# mems.net
KiCad netlist of a schematic drawn in Altium Designer
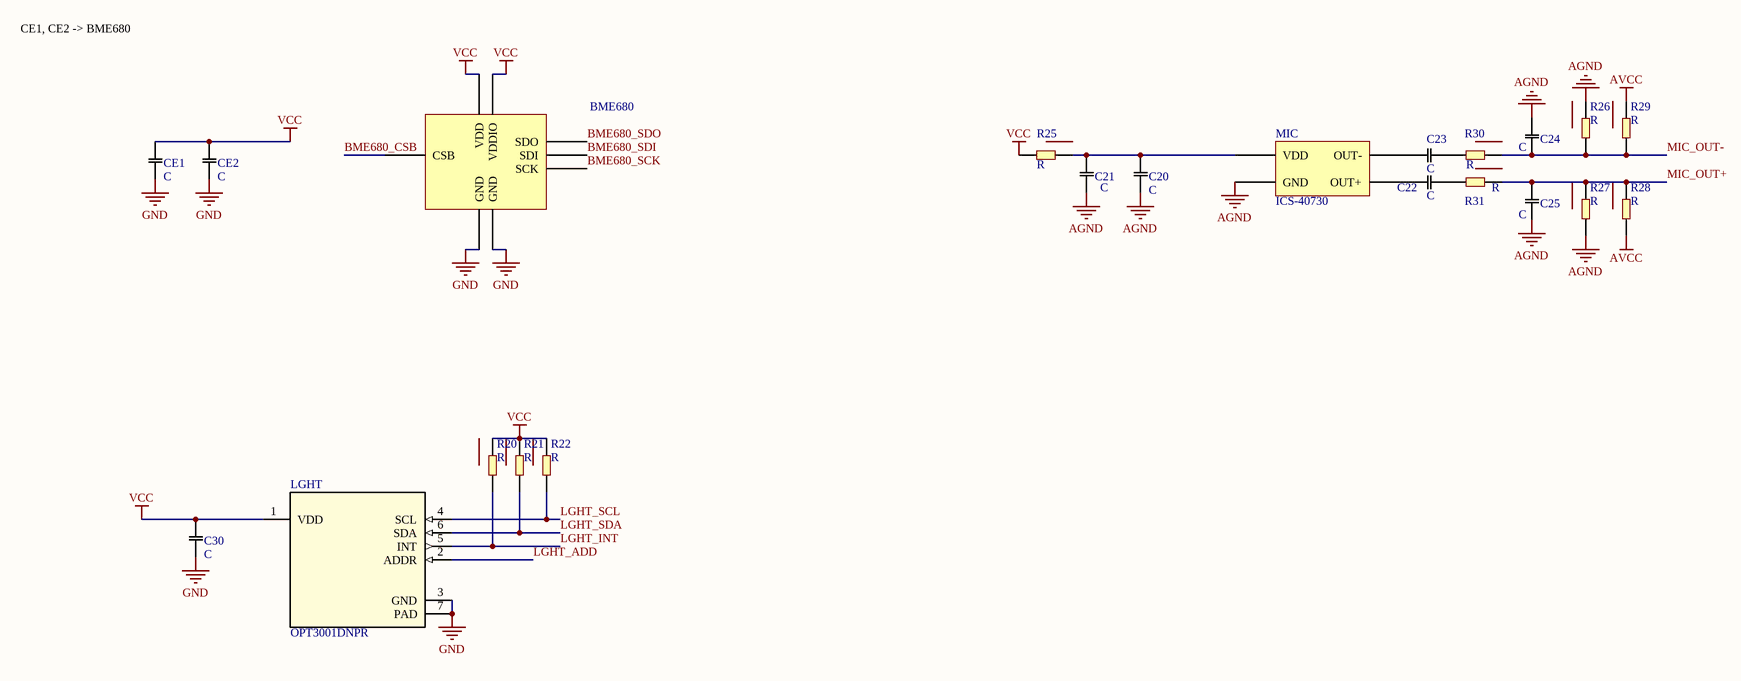
[diagram p0: mems.SchDoc]

(export (version "E")
  (design (tool "Eeschema 10.0.6"))
  (components
    (comp (ref "BME680") (value "~") (footprint "BME680") (libsource (lib "env_sens") (part "BME680")))
    (comp (ref "C20")
      (value "C")
      (footprint "402")
      (description "Capacitor")
      (libsource (lib "pass_comp") (part "C"))
    )
    (comp (ref "C21")
      (value "C")
      (footprint "402")
      (description "Capacitor")
      (libsource (lib "pass_comp") (part "C"))
    )
    (comp (ref "C22")
      (value "C")
      (footprint "402")
      (description "Capacitor")
      (libsource (lib "pass_comp") (part "C"))
    )
    (comp (ref "C23")
      (value "C")
      (footprint "402")
      (description "Capacitor")
      (libsource (lib "pass_comp") (part "C"))
    )
    (comp (ref "C24")
      (value "C")
      (footprint "402")
      (description "Capacitor")
      (libsource (lib "pass_comp") (part "C"))
    )
    (comp (ref "C25")
      (value "C")
      (footprint "402")
      (description "Capacitor")
      (libsource (lib "pass_comp") (part "C"))
    )
    (comp (ref "C30")
      (value "C")
      (footprint "402")
      (description "Capacitor")
      (libsource (lib "pass_comp") (part "C"))
    )
    (comp (ref "CE1")
      (value "C")
      (footprint "402")
      (description "Capacitor")
      (libsource (lib "pass_comp") (part "C"))
    )
    (comp (ref "CE2")
      (value "C")
      (footprint "402")
      (description "Capacitor")
      (libsource (lib "pass_comp") (part "C"))
    )
    (comp (ref "LGHT")
      (value "OPT3001DNPR")
      (footprint "DNP0006A")
      (description "Imported")
      (fields (field (name "PARTNUMBER") "OPT3001DNP") (field (name "MANUFACTURER") "Texas Instruments"))
      (libsource (lib "env_sens") (part "OPT3001DNPR"))
    )
    (comp (ref "MIC")
      (value "ICS-40730")
      (footprint "ICS-40730")
      (libsource (lib "env_sens") (part "ICS-40730"))
    )
    (comp (ref "R20")
      (value "R")
      (footprint "402")
      (description "Resistor")
      (libsource (lib "") (part "R_1"))
    )
    (comp (ref "R21")
      (value "R")
      (footprint "402")
      (description "Resistor")
      (libsource (lib "") (part "R_1"))
    )
    (comp (ref "R22")
      (value "R")
      (footprint "402")
      (description "Resistor")
      (libsource (lib "") (part "R_1"))
    )
    (comp (ref "R25")
      (value "R")
      (footprint "603")
      (description "Resistor")
      (libsource (lib "pass_comp") (part "R"))
    )
    (comp (ref "R26")
      (value "R")
      (footprint "402")
      (description "Resistor")
      (libsource (lib "") (part "R_1"))
    )
    (comp (ref "R27")
      (value "R")
      (footprint "402")
      (description "Resistor")
      (libsource (lib "") (part "R_1"))
    )
    (comp (ref "R28")
      (value "R")
      (footprint "402")
      (description "Resistor")
      (libsource (lib "") (part "R_1"))
    )
    (comp (ref "R29")
      (value "R")
      (footprint "402")
      (description "Resistor")
      (libsource (lib "") (part "R_1"))
    )
    (comp (ref "R30")
      (value "R")
      (footprint "402")
      (description "Resistor")
      (libsource (lib "pass_comp") (part "R"))
    )
    (comp (ref "R31")
      (value "R")
      (footprint "402")
      (description "Resistor")
      (libsource (lib "pass_comp") (part "R"))
    )
  )
  (nets
    (net (code "1") (name "/BME680_CSB") (class "Default")
      (node (ref "BME680") (pin "2") (pinfunction "CSB_2") (pintype "passive"))
    )
    (net (code "2") (name "/BME680_SCK") (class "Default")
      (node (ref "BME680") (pin "4") (pinfunction "SCK_4") (pintype "passive"))
    )
    (net (code "3") (name "/BME680_SDI") (class "Default")
      (node (ref "BME680") (pin "3") (pinfunction "SDI_3") (pintype "passive"))
    )
    (net (code "4") (name "/BME680_SDO") (class "Default")
      (node (ref "BME680") (pin "5") (pinfunction "SDO_5") (pintype "passive"))
    )
    (net (code "5") (name "/LGHT_ADD") (class "Default")
      (node (ref "LGHT") (pin "2") (pinfunction "ADDR_2") (pintype "input"))
    )
    (net (code "6") (name "/LGHT_INT") (class "Default")
      (node (ref "LGHT") (pin "5") (pinfunction "INT_5") (pintype "output"))
      (node (ref "R20") (pin "1") (pintype "passive"))
    )
    (net (code "7") (name "/LGHT_SCL") (class "Default")
      (node (ref "LGHT") (pin "4") (pinfunction "SCL_4") (pintype "input"))
      (node (ref "R22") (pin "1") (pintype "passive"))
    )
    (net (code "8") (name "/LGHT_SDA") (class "Default")
      (node (ref "LGHT") (pin "6") (pinfunction "SDA_6") (pintype "input"))
      (node (ref "R21") (pin "1") (pintype "passive"))
    )
    (net (code "9") (name "/MIC_OUT+") (class "Default")
      (node (ref "C25") (pin "2") (pintype "passive"))
      (node (ref "R27") (pin "2") (pintype "passive"))
      (node (ref "R28") (pin "2") (pintype "passive"))
      (node (ref "R31") (pin "2") (pintype "passive"))
    )
    (net (code "10") (name "/MIC_OUT-") (class "Default")
      (node (ref "C24") (pin "1") (pintype "passive"))
      (node (ref "R26") (pin "1") (pintype "passive"))
      (node (ref "R29") (pin "1") (pintype "passive"))
      (node (ref "R30") (pin "2") (pintype "passive"))
    )
    (net (code "11") (name "AGND") (class "Default")
      (node (ref "C20") (pin "1") (pintype "passive"))
      (node (ref "C21") (pin "1") (pintype "passive"))
      (node (ref "C24") (pin "2") (pintype "passive"))
      (node (ref "C25") (pin "1") (pintype "passive"))
      (node (ref "MIC") (pin "4") (pinfunction "GND_4") (pintype "passive"))
      (node (ref "R26") (pin "2") (pintype "passive"))
      (node (ref "R27") (pin "1") (pintype "passive"))
    )
    (net (code "12") (name "AVCC") (class "Default")
      (node (ref "R28") (pin "1") (pintype "passive"))
      (node (ref "R29") (pin "2") (pintype "passive"))
    )
    (net (code "13") (name "GND") (class "Default")
      (node (ref "BME680") (pin "1") (pinfunction "GND_1") (pintype "passive"))
      (node (ref "BME680") (pin "7") (pinfunction "GND_7") (pintype "passive"))
      (node (ref "C30") (pin "1") (pintype "passive"))
      (node (ref "CE1") (pin "1") (pintype "passive"))
      (node (ref "CE2") (pin "1") (pintype "passive"))
      (node (ref "LGHT") (pin "3") (pinfunction "GND_3") (pintype "power_in"))
      (node (ref "LGHT") (pin "7") (pinfunction "PAD_7") (pintype "passive"))
    )
    (net (code "14") (name "Net-(C22-Pad1)") (class "Default")
      (node (ref "C22") (pin "1") (pintype "passive"))
      (node (ref "R31") (pin "1") (pintype "passive"))
    )
    (net (code "15") (name "Net-(C23-Pad1)") (class "Default")
      (node (ref "C23") (pin "1") (pintype "passive"))
      (node (ref "R30") (pin "1") (pintype "passive"))
    )
    (net (code "16") (name "Net-(MIC-OUT+)") (class "Default")
      (node (ref "C22") (pin "2") (pintype "passive"))
      (node (ref "MIC") (pin "3") (pinfunction "OUT+_3") (pintype "passive"))
    )
    (net (code "17") (name "Net-(MIC-OUT-)") (class "Default")
      (node (ref "C23") (pin "2") (pintype "passive"))
      (node (ref "MIC") (pin "2") (pinfunction "OUT-_2") (pintype "passive"))
    )
    (net (code "18") (name "Net-(MIC-VDD)") (class "Default")
      (node (ref "C20") (pin "2") (pintype "passive"))
      (node (ref "C21") (pin "2") (pintype "passive"))
      (node (ref "MIC") (pin "1") (pinfunction "VDD_1") (pintype "passive"))
      (node (ref "R25") (pin "2") (pintype "passive"))
    )
    (net (code "19") (name "VCC") (class "Default")
      (node (ref "BME680") (pin "6") (pinfunction "VDDIO_6") (pintype "passive"))
      (node (ref "BME680") (pin "8") (pinfunction "VDD_8") (pintype "passive"))
      (node (ref "C30") (pin "2") (pintype "passive"))
      (node (ref "CE1") (pin "2") (pintype "passive"))
      (node (ref "CE2") (pin "2") (pintype "passive"))
      (node (ref "LGHT") (pin "1") (pinfunction "VDD_1") (pintype "power_in"))
      (node (ref "R20") (pin "2") (pintype "passive"))
      (node (ref "R21") (pin "2") (pintype "passive"))
      (node (ref "R22") (pin "2") (pintype "passive"))
      (node (ref "R25") (pin "1") (pintype "passive"))
    )
  )
)
